# AMP_P1.net
KiCad netlist of a schematic drawn in Altium Designer
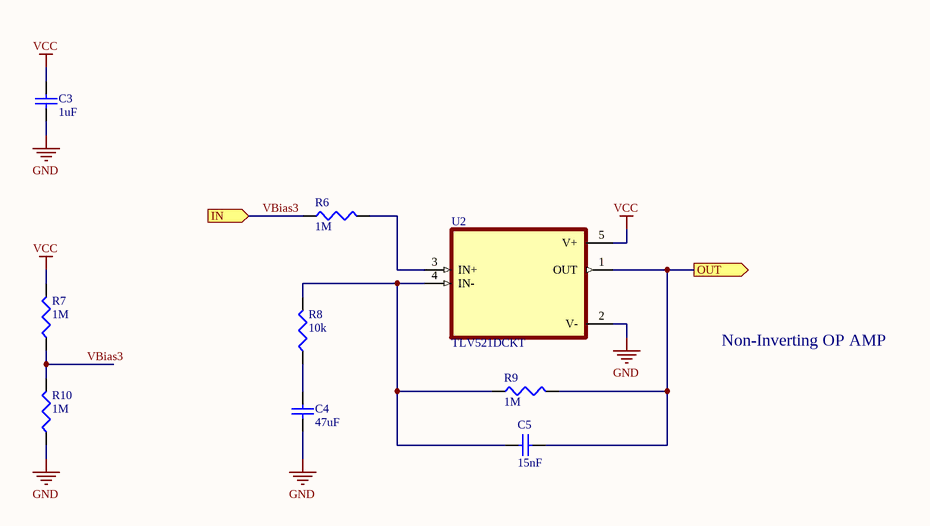
[diagram p0: AMP_P1.schDoc]

(export (version "E")
  (design (tool "Eeschema 10.0.6"))
  (components
    (comp (ref "C3")
      (value "1uF")
      (footprint "SMD-0603")
      (description "Ceramic Capacitor 0603")
      (libsource (lib "LCR") (part "CAP0603"))
    )
    (comp (ref "C4")
      (value "47uF")
      (footprint "SMD-0603")
      (description "Ceramic Capacitor 0603")
      (libsource (lib "LCR") (part "CAP0603"))
    )
    (comp (ref "C5")
      (value "15nF")
      (footprint "SMD-0603")
      (description "Ceramic Capacitor 0603")
      (libsource (lib "LCR") (part "CAP0603"))
    )
    (comp (ref "R6")
      (value "1M")
      (footprint "SMD-0603")
      (description "Resistor-0603")
      (libsource (lib "LCR") (part "RES0603"))
    )
    (comp (ref "R7")
      (value "1M")
      (footprint "SMD-0603")
      (description "Resistor-0603")
      (libsource (lib "LCR") (part "RES0603"))
    )
    (comp (ref "R8")
      (value "10k")
      (footprint "SMD-0603")
      (description "Resistor-0603")
      (libsource (lib "LCR") (part "RES0603"))
    )
    (comp (ref "R9")
      (value "1M")
      (footprint "SMD-0603")
      (description "Resistor-0603")
      (libsource (lib "LCR") (part "RES0603"))
    )
    (comp (ref "R10")
      (value "1M")
      (footprint "SMD-0603")
      (description "Resistor-0603")
      (libsource (lib "LCR") (part "RES0603"))
    )
    (comp (ref "U2")
      (value "TLV521DCKT")
      (footprint "TLV521-SOT-5N")
      (fields (field (name "MF") "Texas Instruments"))
      (libsource (lib "op_amp") (part "TLV521DCKT"))
    )
  )
  (nets
    (net (code "1") (name "/OUT") (class "Default")
      (node (ref "C5") (pin "2") (pinfunction "2_2") (pintype "passive"))
      (node (ref "R9") (pin "2") (pinfunction "2_2") (pintype "passive"))
      (node (ref "U2") (pin "1") (pinfunction "OUT_1") (pintype "output"))
    )
    (net (code "2") (name "/VBias3") (class "Default")
      (node (ref "R10") (pin "2") (pinfunction "2_2") (pintype "passive"))
      (node (ref "R6") (pin "1") (pinfunction "1_1") (pintype "passive"))
      (node (ref "R7") (pin "1") (pinfunction "1_1") (pintype "passive"))
    )
    (net (code "3") (name "GND") (class "Default")
      (node (ref "C3") (pin "1") (pinfunction "1_1") (pintype "passive"))
      (node (ref "C4") (pin "1") (pinfunction "1_1") (pintype "passive"))
      (node (ref "R10") (pin "1") (pinfunction "1_1") (pintype "passive"))
      (node (ref "U2") (pin "2") (pinfunction "V-_2") (pintype "power_in"))
    )
    (net (code "4") (name "Net-(C4-Pad2)") (class "Default")
      (node (ref "C4") (pin "2") (pinfunction "2_2") (pintype "passive"))
      (node (ref "R8") (pin "1") (pinfunction "1_1") (pintype "passive"))
    )
    (net (code "5") (name "Net-(U2-IN+)") (class "Default")
      (node (ref "R6") (pin "2") (pinfunction "2_2") (pintype "passive"))
      (node (ref "U2") (pin "3") (pinfunction "IN+_3") (pintype "input"))
    )
    (net (code "6") (name "Net-(U2-IN-)") (class "Default")
      (node (ref "C5") (pin "1") (pinfunction "1_1") (pintype "passive"))
      (node (ref "R8") (pin "2") (pinfunction "2_2") (pintype "passive"))
      (node (ref "R9") (pin "1") (pinfunction "1_1") (pintype "passive"))
      (node (ref "U2") (pin "4") (pinfunction "IN-_4") (pintype "input"))
    )
    (net (code "7") (name "VCC") (class "Default")
      (node (ref "C3") (pin "2") (pinfunction "2_2") (pintype "passive"))
      (node (ref "R7") (pin "2") (pinfunction "2_2") (pintype "passive"))
      (node (ref "U2") (pin "5") (pinfunction "V+_5") (pintype "power_in"))
    )
  )
)
